# LinearFaders.net
KiCad netlist of a schematic drawn in Altium Designer
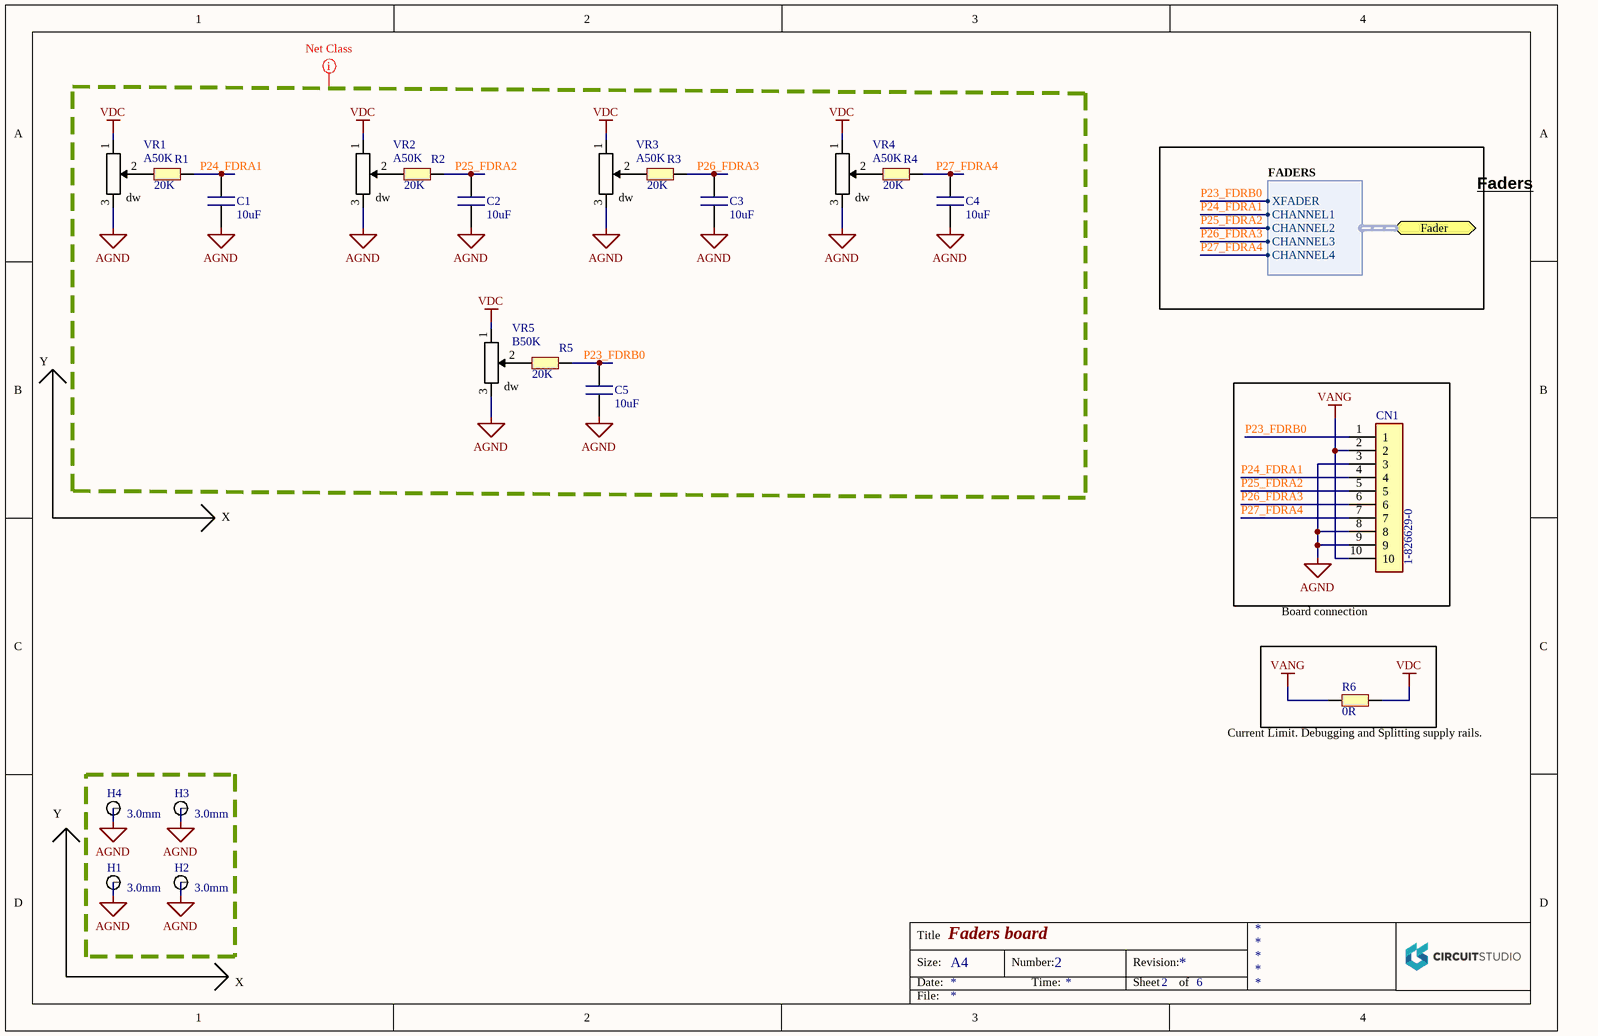
[diagram p0: LinearFaders.SchDoc]

(export (version "E")
  (design (tool "Eeschema 10.0.6"))
  (components
    (comp (ref "C1")
      (value "10uF")
      (footprint "CAP 0603 10uF")
      (description "16V 10uF X5R ±20% 0603 MLCC")
      (fields (field (name "TOLERANCE") "20%") (field (name "MP") "CS1608X5R106M160NRB"))
      (libsource (lib "[0002]CAP0603_SMD_10uF") (part "CAP 0603 10uF"))
    )
    (comp (ref "C2")
      (value "10uF")
      (footprint "CAP 0603 10uF")
      (description "16V 10uF X5R ±20% 0603 MLCC")
      (fields (field (name "TOLERANCE") "20%") (field (name "MP") "CS1608X5R106M160NRB"))
      (libsource (lib "[0002]CAP0603_SMD_10uF") (part "CAP 0603 10uF"))
    )
    (comp (ref "C3")
      (value "10uF")
      (footprint "CAP 0603 10uF")
      (description "16V 10uF X5R ±20% 0603 MLCC")
      (fields (field (name "TOLERANCE") "20%") (field (name "MP") "CS1608X5R106M160NRB"))
      (libsource (lib "[0002]CAP0603_SMD_10uF") (part "CAP 0603 10uF"))
    )
    (comp (ref "C4")
      (value "10uF")
      (footprint "CAP 0603 10uF")
      (description "16V 10uF X5R ±20% 0603 MLCC")
      (fields (field (name "TOLERANCE") "20%") (field (name "MP") "CS1608X5R106M160NRB"))
      (libsource (lib "[0002]CAP0603_SMD_10uF") (part "CAP 0603 10uF"))
    )
    (comp (ref "C5")
      (value "10uF")
      (footprint "CAP 0603 10uF")
      (description "16V 10uF X5R ±20% 0603 MLCC")
      (fields (field (name "TOLERANCE") "20%") (field (name "MP") "CS1608X5R106M160NRB"))
      (libsource (lib "[0002]CAP0603_SMD_10uF") (part "CAP 0603 10uF"))
    )
    (comp (ref "CN1")
      (value "1-826629-0")
      (footprint "TE_1-826629-0")
      (description "Conn Unshrouded Header HDR 10 POS 2.54mm Solder ST Thru-Hole Carton")
      (fields (field (name "MF") "TE Connectivity"))
      (libsource (lib "[0503]HEADER10X1X2_54_TH_ST") (part "1-826629-0"))
    )
    (comp (ref "H1")
      (value "3.0mm")
      (footprint "HOLE-3.0MM+PAD")
      (description "3.0mm HOLE+6mmPAD")
      (libsource (lib "[1001]HOLE_PLATED_3MM") (part "3.0MM HOLE+6mmPAD"))
    )
    (comp (ref "H2")
      (value "3.0mm")
      (footprint "HOLE-3.0MM+PAD")
      (description "3.0mm HOLE+6mmPAD")
      (libsource (lib "[1001]HOLE_PLATED_3MM") (part "3.0MM HOLE+6mmPAD"))
    )
    (comp (ref "H3")
      (value "3.0mm")
      (footprint "HOLE-3.0MM+PAD")
      (description "3.0mm HOLE+6mmPAD")
      (libsource (lib "[1001]HOLE_PLATED_3MM") (part "3.0MM HOLE+6mmPAD"))
    )
    (comp (ref "H4")
      (value "3.0mm")
      (footprint "HOLE-3.0MM+PAD")
      (description "3.0mm HOLE+6mmPAD")
      (libsource (lib "[1001]HOLE_PLATED_3MM") (part "3.0MM HOLE+6mmPAD"))
    )
    (comp (ref "R1")
      (value "20K")
      (footprint "RES 0603 20K")
      (description "0603 Standard 20K Resistor, 1%, 100mW, ±200ppm/℃,Thick Film")
      (fields (field (name "MP") "ETCR0603F20K0K9"))
      (libsource (lib "[0001]RES0603_SMD_20K") (part "RES0603_20K"))
    )
    (comp (ref "R2")
      (value "20K")
      (footprint "RES 0603 20K")
      (description "0603 Standard 20K Resistor, 1%, 100mW, ±200ppm/℃,Thick Film")
      (fields (field (name "MP") "ETCR0603F20K0K9"))
      (libsource (lib "[0001]RES0603_SMD_20K") (part "RES0603_20K"))
    )
    (comp (ref "R3")
      (value "20K")
      (footprint "RES 0603 20K")
      (description "0603 Standard 20K Resistor, 1%, 100mW, ±200ppm/℃,Thick Film")
      (fields (field (name "MP") "ETCR0603F20K0K9"))
      (libsource (lib "[0001]RES0603_SMD_20K") (part "RES0603_20K"))
    )
    (comp (ref "R4")
      (value "20K")
      (footprint "RES 0603 20K")
      (description "0603 Standard 20K Resistor, 1%, 100mW, ±200ppm/℃,Thick Film")
      (fields (field (name "MP") "ETCR0603F20K0K9"))
      (libsource (lib "[0001]RES0603_SMD_20K") (part "RES0603_20K"))
    )
    (comp (ref "R5")
      (value "20K")
      (footprint "RES 0603 20K")
      (description "0603 Standard 20K Resistor, 1%, 100mW, ±200ppm/℃,Thick Film")
      (fields (field (name "MP") "ETCR0603F20K0K9"))
      (libsource (lib "[0001]RES0603_SMD_20K") (part "RES0603_20K"))
    )
    (comp (ref "R6")
      (value "0R")
      (footprint "RES 0603")
      (description "0603 Standard 0R Resistor, 1%, 100mW, ±200ppm/℃,Thick Film")
      (fields (field (name "MP") "AF0603FR-070RL"))
      (libsource (lib "[0001]RES0603_SMD_0R") (part "RES0603_0R"))
    )
    (comp (ref "VR1")
      (value "A50K")
      (footprint "PTA4543")
      (description "Slide Potentiometers PANEL CONTROL - SLIDE CARBON")
      (fields (field (name "MP") "PTA4543-2015CPA503"))
      (libsource (lib "[0009]PTA4543-2015CPA503") (part "PTA4543-2015CPA503"))
    )
    (comp (ref "VR2")
      (value "A50K")
      (footprint "PTA4543")
      (description "Slide Potentiometers PANEL CONTROL - SLIDE CARBON")
      (fields (field (name "MP") "PTA4543-2015CPA503"))
      (libsource (lib "[0009]PTA4543-2015CPA503") (part "PTA4543-2015CPA503"))
    )
    (comp (ref "VR3")
      (value "A50K")
      (footprint "PTA4543")
      (description "Slide Potentiometers PANEL CONTROL - SLIDE CARBON")
      (fields (field (name "MP") "PTA4543-2015CPA503"))
      (libsource (lib "[0009]PTA4543-2015CPA503") (part "PTA4543-2015CPA503"))
    )
    (comp (ref "VR4")
      (value "A50K")
      (footprint "PTA4543")
      (description "Slide Potentiometers PANEL CONTROL - SLIDE CARBON")
      (fields (field (name "MP") "PTA4543-2015CPA503"))
      (libsource (lib "[0009]PTA4543-2015CPA503") (part "PTA4543-2015CPA503"))
    )
    (comp (ref "VR5")
      (value "B50K")
      (footprint "PTA4543")
      (description "Slide Potentiometers PANEL CONTROL - SLIDE CARBON")
      (fields (field (name "MP") "PTA4543-2015CPB503"))
      (libsource (lib "[0009]PTA4543-2015CPB503") (part "PTA4543-2015CPB503"))
    )
  )
  (nets
    (net (code "2") (name "/P23_FDRB0") (class "Default")
      (node (ref "C5") (pin "2") (pinfunction "2_2") (pintype "passive"))
      (node (ref "CN1") (pin "1") (pinfunction "1_1") (pintype "passive"))
      (node (ref "R5") (pin "2") (pinfunction "2_2") (pintype "passive"))
    )
    (net (code "3") (name "/P24_FDRA1") (class "Default")
      (node (ref "C1") (pin "2") (pinfunction "2_2") (pintype "passive"))
      (node (ref "CN1") (pin "4") (pinfunction "4_4") (pintype "passive"))
      (node (ref "R1") (pin "2") (pinfunction "2_2") (pintype "passive"))
    )
    (net (code "4") (name "/P25_FDRA2") (class "Default")
      (node (ref "C2") (pin "2") (pinfunction "2_2") (pintype "passive"))
      (node (ref "CN1") (pin "5") (pinfunction "5_5") (pintype "passive"))
      (node (ref "R2") (pin "2") (pinfunction "2_2") (pintype "passive"))
    )
    (net (code "5") (name "/P26_FDRA3") (class "Default")
      (node (ref "C3") (pin "2") (pinfunction "2_2") (pintype "passive"))
      (node (ref "CN1") (pin "6") (pinfunction "6_6") (pintype "passive"))
      (node (ref "R3") (pin "2") (pinfunction "2_2") (pintype "passive"))
    )
    (net (code "6") (name "/P27_FDRA4") (class "Default")
      (node (ref "C4") (pin "2") (pinfunction "2_2") (pintype "passive"))
      (node (ref "CN1") (pin "7") (pinfunction "7_7") (pintype "passive"))
      (node (ref "R4") (pin "2") (pinfunction "2_2") (pintype "passive"))
    )
    (net (code "8") (name "AGND") (class "Default")
      (node (ref "C1") (pin "1") (pinfunction "1_1") (pintype "passive"))
      (node (ref "C2") (pin "1") (pinfunction "1_1") (pintype "passive"))
      (node (ref "C3") (pin "1") (pinfunction "1_1") (pintype "passive"))
      (node (ref "C4") (pin "1") (pinfunction "1_1") (pintype "passive"))
      (node (ref "C5") (pin "1") (pinfunction "1_1") (pintype "passive"))
      (node (ref "CN1") (pin "3") (pinfunction "3_3") (pintype "passive"))
      (node (ref "CN1") (pin "8") (pinfunction "8_8") (pintype "passive"))
      (node (ref "CN1") (pin "9") (pinfunction "9_9") (pintype "passive"))
      (node (ref "H1") (pin "1") (pinfunction "1_1") (pintype "passive"))
      (node (ref "H2") (pin "1") (pinfunction "1_1") (pintype "passive"))
      (node (ref "H3") (pin "1") (pinfunction "1_1") (pintype "passive"))
      (node (ref "H4") (pin "1") (pinfunction "1_1") (pintype "passive"))
      (node (ref "VR1") (pin "3") (pintype "passive"))
      (node (ref "VR2") (pin "3") (pintype "passive"))
      (node (ref "VR3") (pin "3") (pintype "passive"))
      (node (ref "VR4") (pin "3") (pintype "passive"))
      (node (ref "VR5") (pin "3") (pintype "passive"))
    )
    (net (code "9") (name "Net-(R1-Pad1)") (class "Default")
      (node (ref "R1") (pin "1") (pinfunction "1_1") (pintype "passive"))
      (node (ref "VR1") (pin "2") (pintype "passive"))
    )
    (net (code "10") (name "Net-(R2-Pad1)") (class "Default")
      (node (ref "R2") (pin "1") (pinfunction "1_1") (pintype "passive"))
      (node (ref "VR2") (pin "2") (pintype "passive"))
    )
    (net (code "11") (name "Net-(R3-Pad1)") (class "Default")
      (node (ref "R3") (pin "1") (pinfunction "1_1") (pintype "passive"))
      (node (ref "VR3") (pin "2") (pintype "passive"))
    )
    (net (code "12") (name "Net-(R4-Pad1)") (class "Default")
      (node (ref "R4") (pin "1") (pinfunction "1_1") (pintype "passive"))
      (node (ref "VR4") (pin "2") (pintype "passive"))
    )
    (net (code "13") (name "Net-(R5-Pad1)") (class "Default")
      (node (ref "R5") (pin "1") (pinfunction "1_1") (pintype "passive"))
      (node (ref "VR5") (pin "2") (pintype "passive"))
    )
    (net (code "14") (name "VANG") (class "Default")
      (node (ref "CN1") (pin "10") (pinfunction "10_10") (pintype "passive"))
      (node (ref "CN1") (pin "2") (pinfunction "2_2") (pintype "passive"))
      (node (ref "R6") (pin "1") (pinfunction "1_1") (pintype "passive"))
    )
    (net (code "15") (name "VDC") (class "Default")
      (node (ref "R6") (pin "2") (pinfunction "2_2") (pintype "passive"))
      (node (ref "VR1") (pin "1") (pintype "passive"))
      (node (ref "VR2") (pin "1") (pintype "passive"))
      (node (ref "VR3") (pin "1") (pintype "passive"))
      (node (ref "VR4") (pin "1") (pintype "passive"))
      (node (ref "VR5") (pin "1") (pintype "passive"))
    )
  )
)
